# LightSensorWiring.net
KiCad netlist of a schematic drawn in EAGLE
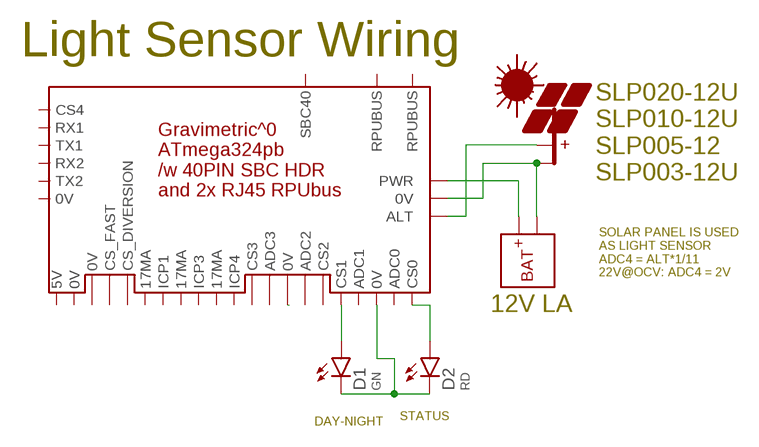
[diagram p0: schematic, sheet 1]

(export (version "E")
  (design (tool "Eeschema 10.0.6"))
  (components
    (comp (ref "D1")
      (value "GN")
      (footprint "eagle-import:LED5MM")
      (libsource (lib "eagle-import") (part "LED5MM"))
    )
    (comp (ref "D2")
      (value "RD")
      (footprint "eagle-import:LED5MM")
      (libsource (lib "eagle-import") (part "LED5MM"))
    )
    (comp (ref "PV4")
      (value "PV")
      (footprint "eagle-import:NA-30")
      (libsource (lib "eagle-import") (part "PV"))
    )
    (comp (ref "U$1")
      (value "GRAVIMETRIC")
      (footprint "eagle-import:WITH_RPU_NAMES")
      (libsource (lib "eagle-import") (part "GRAVIMETRIC"))
    )
    (comp (ref "U$7")
      (value "BAT")
      (footprint "eagle-import:NA-30")
      (libsource (lib "eagle-import") (part "BAT"))
    )
  )
  (nets
    (net (code "1") (name "Net-(D1-PadK)") (class "Default")
      (node (ref "D1") (pin "K") (pinfunction "K_K") (pintype "passive"))
      (node (ref "D2") (pin "K") (pinfunction "K_K") (pintype "passive"))
      (node (ref "U$1") (pin "0V@ADC1") (pinfunction "0V_0V@ADC1") (pintype "bidirectional"))
    )
    (net (code "2") (name "Net-(PV4-+PV)") (class "Default")
      (node (ref "PV4") (pin "1") (pinfunction "+PV_1") (pintype "bidirectional"))
      (node (ref "U$1") (pin "BAT") (pinfunction "ALT_BAT") (pintype "bidirectional"))
    )
    (net (code "3") (name "Net-(PV4--PV)") (class "Default")
      (node (ref "PV4") (pin "2") (pinfunction "-PV_2") (pintype "bidirectional"))
      (node (ref "U$1") (pin "0V@PWR") (pinfunction "0V_0V@PWR") (pintype "bidirectional"))
      (node (ref "U$7") (pin "2") (pinfunction "-BAT_2") (pintype "bidirectional"))
    )
    (net (code "4") (name "Net-(U$1-CS0)") (class "Default")
      (node (ref "D2") (pin "A") (pinfunction "A_A") (pintype "passive"))
      (node (ref "U$1") (pin "22MA@ADC1") (pinfunction "CS0_22MA@ADC1") (pintype "bidirectional"))
    )
    (net (code "5") (name "Net-(U$1-CS1)") (class "Default")
      (node (ref "D1") (pin "A") (pinfunction "A_A") (pintype "passive"))
      (node (ref "U$1") (pin "22MA@ADC0") (pinfunction "CS1_22MA@ADC0") (pintype "bidirectional"))
    )
    (net (code "6") (name "Net-(U$7-+BAT)") (class "Default")
      (node (ref "U$1") (pin "PWR") (pinfunction "PWR_PWR") (pintype "bidirectional"))
      (node (ref "U$7") (pin "1") (pinfunction "+BAT_1") (pintype "bidirectional"))
    )
    (net (code "7") (name "unconnected-(U$1-0V-Pad0V@ADC2)") (class "Default")
      (node (ref "U$1") (pin "0V@ADC2") (pinfunction "0V_0V@ADC2") (pintype "bidirectional"))
    )
    (net (code "8") (name "unconnected-(U$1-0V-Pad0V@DIO2)") (class "Default")
      (node (ref "U$1") (pin "0V@DIO2") (pinfunction "0V_0V@DIO2") (pintype "bidirectional"))
    )
    (net (code "9") (name "unconnected-(U$1-0V-Pad0V@DIO9)") (class "Default")
      (node (ref "U$1") (pin "0V@DIO9") (pinfunction "0V_0V@DIO9") (pintype "bidirectional"))
    )
    (net (code "10") (name "unconnected-(U$1-17MA-Pad17MA@ICP1)") (class "Default")
      (node (ref "U$1") (pin "17MA@ICP1") (pinfunction "17MA_17MA@ICP1") (pintype "bidirectional"))
    )
    (net (code "11") (name "unconnected-(U$1-17MA-Pad17MA@ICP3)") (class "Default")
      (node (ref "U$1") (pin "17MA@ICP3") (pinfunction "17MA_17MA@ICP3") (pintype "bidirectional"))
    )
    (net (code "12") (name "unconnected-(U$1-17MA-Pad17MA@ICP4)") (class "Default")
      (node (ref "U$1") (pin "17MA@ICP4") (pinfunction "17MA_17MA@ICP4") (pintype "bidirectional"))
    )
    (net (code "13") (name "unconnected-(U$1-ADC0-PadADC1)") (class "Default")
      (node (ref "U$1") (pin "ADC1") (pinfunction "ADC0_ADC1") (pintype "bidirectional"))
    )
    (net (code "14") (name "unconnected-(U$1-ADC1-PadADC0)") (class "Default")
      (node (ref "U$1") (pin "ADC0") (pinfunction "ADC1_ADC0") (pintype "bidirectional"))
    )
    (net (code "15") (name "unconnected-(U$1-CS2-Pad22MA@ADC2)") (class "Default")
      (node (ref "U$1") (pin "22MA@ADC2") (pinfunction "CS2_22MA@ADC2") (pintype "bidirectional"))
    )
    (net (code "16") (name "unconnected-(U$1-CS3-Pad22MA@ADC3)") (class "Default")
      (node (ref "U$1") (pin "22MA@ADC3") (pinfunction "CS3_22MA@ADC3") (pintype "bidirectional"))
    )
    (net (code "17") (name "unconnected-(U$1-CS4-Pad22MA@ADC4)") (class "Default")
      (node (ref "U$1") (pin "22MA@ADC4") (pinfunction "CS4_22MA@ADC4") (pintype "bidirectional"))
    )
    (net (code "18") (name "unconnected-(U$1-CS_DIVERSION-Pad22MA@DIO2)") (class "Default")
      (node (ref "U$1") (pin "22MA@DIO2") (pinfunction "CS_DIVERSION_22MA@DIO2") (pintype "bidirectional"))
    )
    (net (code "19") (name "unconnected-(U$1-CS_FAST-Pad22MA@DIO9)") (class "Default")
      (node (ref "U$1") (pin "22MA@DIO9") (pinfunction "CS_FAST_22MA@DIO9") (pintype "bidirectional"))
    )
    (net (code "20") (name "unconnected-(U$1-Pad0V)") (class "Default")
      (node (ref "U$1") (pin "0V") (pinfunction "0V_0V") (pintype "bidirectional"))
    )
    (net (code "21") (name "unconnected-(U$1-Pad5V)") (class "Default")
      (node (ref "U$1") (pin "5V") (pinfunction "5V_5V") (pintype "bidirectional"))
    )
    (net (code "22") (name "unconnected-(U$1-PadADC2)") (class "Default")
      (node (ref "U$1") (pin "ADC2") (pinfunction "ADC2_ADC2") (pintype "bidirectional"))
    )
    (net (code "23") (name "unconnected-(U$1-PadADC3)") (class "Default")
      (node (ref "U$1") (pin "ADC3") (pinfunction "ADC3_ADC3") (pintype "bidirectional"))
    )
    (net (code "24") (name "unconnected-(U$1-PadICP1)") (class "Default")
      (node (ref "U$1") (pin "ICP1") (pinfunction "ICP1_ICP1") (pintype "bidirectional"))
    )
    (net (code "25") (name "unconnected-(U$1-PadICP3)") (class "Default")
      (node (ref "U$1") (pin "ICP3") (pinfunction "ICP3_ICP3") (pintype "bidirectional"))
    )
    (net (code "26") (name "unconnected-(U$1-PadICP4)") (class "Default")
      (node (ref "U$1") (pin "ICP4") (pinfunction "ICP4_ICP4") (pintype "bidirectional"))
    )
    (net (code "27") (name "unconnected-(U$1-RPUBUS-Pad+RX)") (class "Default")
      (node (ref "U$1") (pin "+RX") (pinfunction "RPUBUS_+RX") (pintype "bidirectional"))
    )
    (net (code "28") (name "unconnected-(U$1-RPUBUS-Pad+TX)") (class "Default")
      (node (ref "U$1") (pin "+TX") (pinfunction "RPUBUS_+TX") (pintype "bidirectional"))
    )
    (net (code "29") (name "unconnected-(U$1-RX1-PadK1)") (class "Default")
      (node (ref "U$1") (pin "K1") (pinfunction "RX1_K1") (pintype "bidirectional"))
    )
    (net (code "30") (name "unconnected-(U$1-RX2-PadK2)") (class "Default")
      (node (ref "U$1") (pin "K2") (pinfunction "RX2_K2") (pintype "bidirectional"))
    )
    (net (code "31") (name "unconnected-(U$1-SBC40-PadSPI)") (class "Default")
      (node (ref "U$1") (pin "SPI") (pinfunction "SBC40_SPI") (pintype "bidirectional"))
    )
    (net (code "32") (name "unconnected-(U$1-TX1-PadK3)") (class "Default")
      (node (ref "U$1") (pin "K3") (pinfunction "TX1_K3") (pintype "bidirectional"))
    )
    (net (code "33") (name "unconnected-(U$1-TX2-PadK4)") (class "Default")
      (node (ref "U$1") (pin "K4") (pinfunction "TX2_K4") (pintype "bidirectional"))
    )
  )
)
